# SilentBotStep.net
KiCad netlist of a schematic drawn in Altium Designer
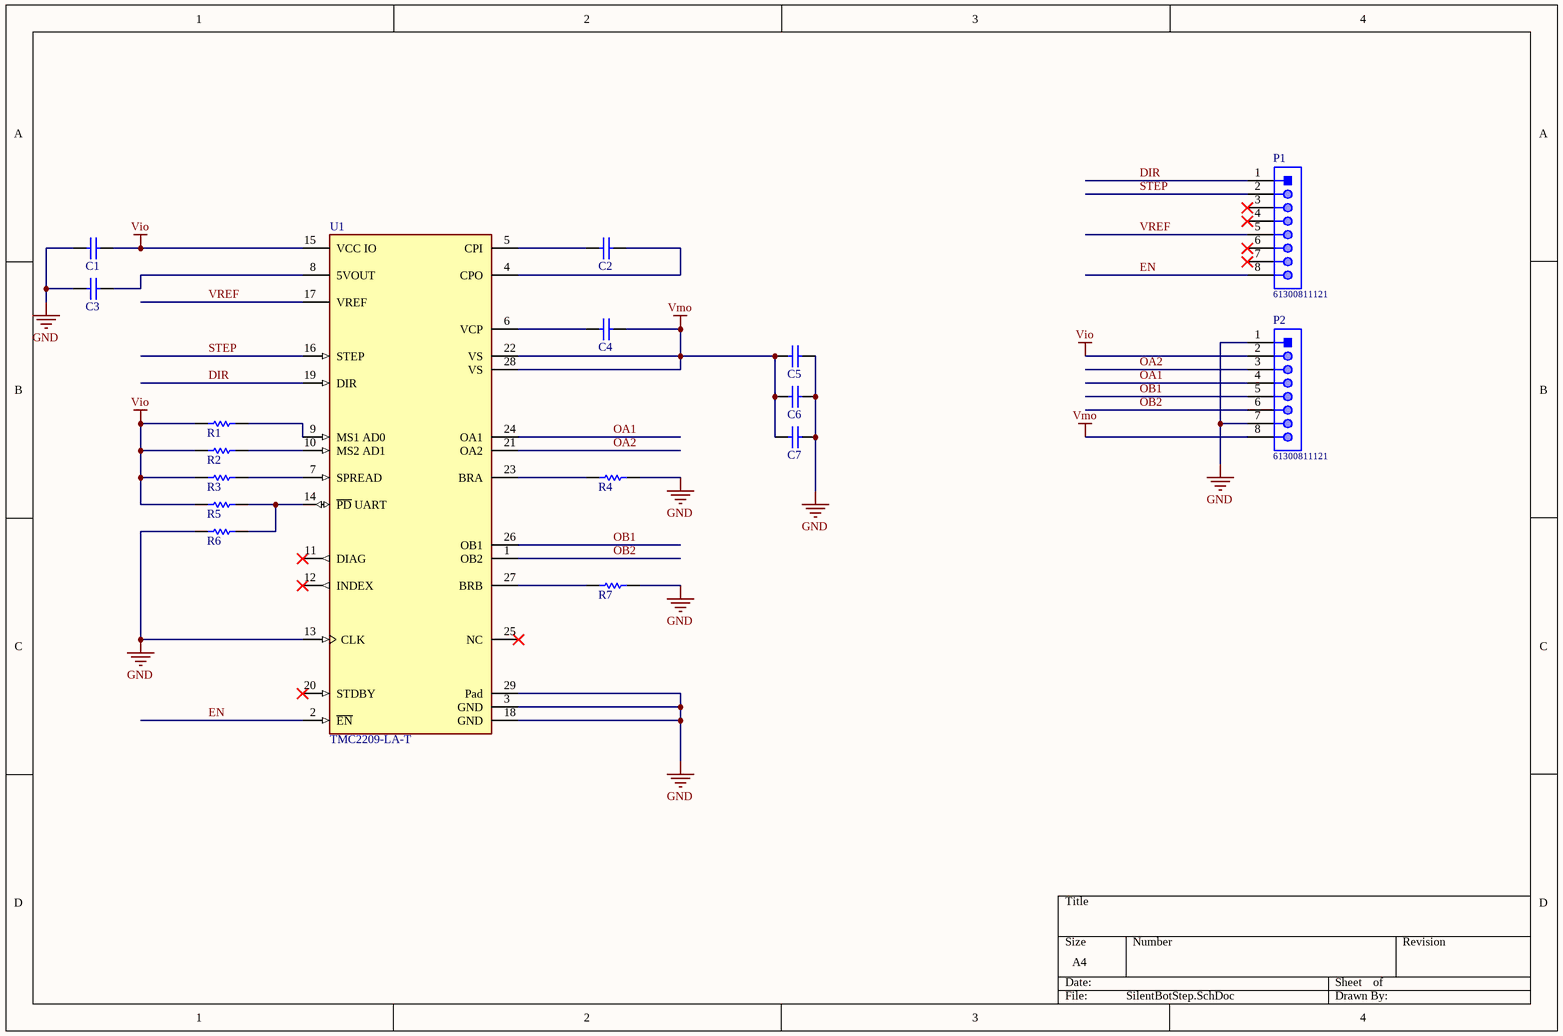
[diagram p0: SilentBotStep.SchDoc]

(export (version "E")
  (design (tool "Eeschema 10.0.6"))
  (components
    (comp (ref "C1")
      (value "GRM155R71H104KE14D")
      (footprint "CAPC1005X55X25LL05T10")
      (description "MURATA - GRM155R71H104KE14D - CAP, MLCC, X7R, 0.1UF, 50V, 0402")
      (fields (field (name "TOLERANCE") "10%") (field (name "VOLTAGE") "50V"))
      (libsource (lib "LTY LLC") (part "CAP"))
    )
    (comp (ref "C2")
      (value "CC0402KRX7R9BB223")
      (footprint "CAPC1005X55X25LL05T10")
      (description "Multilayer Ceramic Capacitors MLCC - SMD/SMT 22K pF 10% 50 Volts")
      (fields (field (name "TOLERANCE") "10%"))
      (libsource (lib "LTY LLC") (part "CAP"))
    )
    (comp (ref "C3")
      (value "GRM155R60J475ME47D")
      (footprint "CAPC1005X55X25LL05T10")
      (description "CAP CER 4.7UF 6.3V X5R 0402")
      (fields (field (name "VOLTAGE") "6.3V") (field (name "TOLERANCE") "20%"))
      (libsource (lib "LTY LLC") (part "CAP"))
    )
    (comp (ref "C4")
      (value "GRM155R71H104KE14D")
      (footprint "CAPC1005X55X25LL05T10")
      (description "MURATA - GRM155R71H104KE14D - CAP, MLCC, X7R, 0.1UF, 50V, 0402")
      (fields (field (name "TOLERANCE") "10%") (field (name "VOLTAGE") "50V"))
      (libsource (lib "LTY LLC") (part "CAP"))
    )
    (comp (ref "C5")
      (value "GRM155R71H104KE14D")
      (footprint "CAPC1005X55X25LL05T10")
      (description "MURATA - GRM155R71H104KE14D - CAP, MLCC, X7R, 0.1UF, 50V, 0402")
      (fields (field (name "TOLERANCE") "10%") (field (name "VOLTAGE") "50V"))
      (libsource (lib "LTY LLC") (part "CAP"))
    )
    (comp (ref "C6")
      (value "GRM155R71H104KE14D")
      (footprint "CAPC1005X55X25LL05T10")
      (description "MURATA - GRM155R71H104KE14D - CAP, MLCC, X7R, 0.1UF, 50V, 0402")
      (fields (field (name "TOLERANCE") "10%") (field (name "VOLTAGE") "50V"))
      (libsource (lib "LTY LLC") (part "CAP"))
    )
    (comp (ref "C7")
      (value "C3216X7R1V106M160AC")
      (footprint "CAPC3216X180X20LL20")
      (fields (field (name "TOLERANCE") "20%"))
      (libsource (lib "LTY LLC") (part "CAP-NP-2"))
    )
    (comp (ref "P1")
      (value "61300811121")
      (footprint "61300811121")
      (description "Board-To-Board Connector, Vertical, Wr-Phd Series, Through Hole, Header, 8, 2.54 Mm")
      (libsource (lib "LTY LLC") (part "WE-CN-1P-M-R8"))
    )
    (comp (ref "P2")
      (value "61300811121")
      (footprint "61300811121")
      (description "Board-To-Board Connector, Vertical, Wr-Phd Series, Through Hole, Header, 8, 2.54 Mm")
      (libsource (lib "LTY LLC") (part "WE-CN-1P-M-R8"))
    )
    (comp (ref "R1")
      (value "RC0402JR-070RL")
      (footprint "RESC1005X40X25LL05T10")
      (description "YAGEO - RC0402JR-070RL. - RES, THICK FILM, 0R, 0.0625W, 0402")
      (fields (field (name "TOLERANCE") "5%"))
      (libsource (lib "LTY LLC") (part "RES"))
    )
    (comp (ref "R2")
      (value "RC0402JR-070RL")
      (footprint "RESC1005X40X25LL05T10")
      (description "YAGEO - RC0402JR-070RL. - RES, THICK FILM, 0R, 0.0625W, 0402")
      (fields (field (name "TOLERANCE") "5%"))
      (libsource (lib "LTY LLC") (part "RES"))
    )
    (comp (ref "R3")
      (value "RC0402JR-070RL")
      (footprint "RESC1005X40X25LL05T10")
      (description "YAGEO - RC0402JR-070RL. - RES, THICK FILM, 0R, 0.0625W, 0402")
      (fields (field (name "TOLERANCE") "5%"))
      (libsource (lib "LTY LLC") (part "RES"))
    )
    (comp (ref "R4")
      (value "ERJ-U6QFR27V")
      (footprint "RESC2013X50X40LL20T20")
      (description "RES 0.27 OHM 1% 1/4W 0805")
      (fields (field (name "TOLERANCE") "1%"))
      (libsource (lib "LTY LLC") (part "RES"))
    )
    (comp (ref "R5")
      (value "RC0402JR-070RL")
      (footprint "RESC1005X40X25LL05T10")
      (description "YAGEO - RC0402JR-070RL. - RES, THICK FILM, 0R, 0.0625W, 0402")
      (fields (field (name "TOLERANCE") "5%"))
      (libsource (lib "LTY LLC") (part "RES"))
    )
    (comp (ref "R6")
      (value "RC0402JR-070RL")
      (footprint "RESC1005X40X25LL05T10")
      (description "YAGEO - RC0402JR-070RL. - RES, THICK FILM, 0R, 0.0625W, 0402")
      (fields (field (name "TOLERANCE") "5%"))
      (libsource (lib "LTY LLC") (part "RES"))
    )
    (comp (ref "R7")
      (value "ERJ-U6QFR27V")
      (footprint "RESC2013X50X40LL20T20")
      (description "RES 0.27 OHM 1% 1/4W 0805")
      (fields (field (name "TOLERANCE") "1%"))
      (libsource (lib "LTY LLC") (part "RES"))
    )
    (comp (ref "U1")
      (value "TMC2209-LA-T")
      (footprint "Trinamic_0_IPC_C")
      (description "Motor Driver, Stepper, QFN-28")
      (libsource (lib "LTY LLC") (part "TMC2209-LA"))
    )
  )
  (nets
    (net (code "1") (name "/DIR") (class "Default")
      (node (ref "P1") (pin "1") (pinfunction "1_1") (pintype "passive"))
      (node (ref "U1") (pin "19") (pinfunction "DIR_19") (pintype "input"))
    )
    (net (code "2") (name "/EN") (class "Default")
      (node (ref "P1") (pin "8") (pinfunction "8_8") (pintype "passive"))
      (node (ref "U1") (pin "2") (pinfunction "~{EN}_2") (pintype "input"))
    )
    (net (code "3") (name "/OA1") (class "Default")
      (node (ref "P2") (pin "4") (pinfunction "4_4") (pintype "passive"))
      (node (ref "U1") (pin "24") (pinfunction "OA1_24") (pintype "passive"))
    )
    (net (code "4") (name "/OA2") (class "Default")
      (node (ref "P2") (pin "3") (pinfunction "3_3") (pintype "passive"))
      (node (ref "U1") (pin "21") (pinfunction "OA2_21") (pintype "passive"))
    )
    (net (code "5") (name "/OB1") (class "Default")
      (node (ref "P2") (pin "5") (pinfunction "5_5") (pintype "passive"))
      (node (ref "U1") (pin "26") (pinfunction "OB1_26") (pintype "passive"))
    )
    (net (code "6") (name "/OB2") (class "Default")
      (node (ref "P2") (pin "6") (pinfunction "6_6") (pintype "passive"))
      (node (ref "U1") (pin "1") (pinfunction "OB2_1") (pintype "passive"))
    )
    (net (code "7") (name "/STEP") (class "Default")
      (node (ref "P1") (pin "2") (pinfunction "2_2") (pintype "passive"))
      (node (ref "U1") (pin "16") (pinfunction "STEP_16") (pintype "input"))
    )
    (net (code "8") (name "/VREF") (class "Default")
      (node (ref "P1") (pin "5") (pinfunction "5_5") (pintype "passive"))
      (node (ref "U1") (pin "17") (pinfunction "VREF_17") (pintype "passive"))
    )
    (net (code "9") (name "GND") (class "Default")
      (node (ref "C1") (pin "1") (pinfunction "1_1") (pintype "passive"))
      (node (ref "C3") (pin "1") (pinfunction "1_1") (pintype "passive"))
      (node (ref "C5") (pin "2") (pinfunction "2_2") (pintype "passive"))
      (node (ref "C6") (pin "2") (pinfunction "2_2") (pintype "passive"))
      (node (ref "C7") (pin "2") (pinfunction "2_2") (pintype "passive"))
      (node (ref "P2") (pin "1") (pinfunction "1_1") (pintype "passive"))
      (node (ref "P2") (pin "7") (pinfunction "7_7") (pintype "passive"))
      (node (ref "R4") (pin "2") (pinfunction "2_2") (pintype "passive"))
      (node (ref "R6") (pin "1") (pinfunction "1_1") (pintype "passive"))
      (node (ref "R7") (pin "2") (pinfunction "2_2") (pintype "passive"))
      (node (ref "U1") (pin "13") (pinfunction "CLK_13") (pintype "input"))
      (node (ref "U1") (pin "18") (pinfunction "GND_18") (pintype "power_in"))
      (node (ref "U1") (pin "29") (pinfunction "Pad_29") (pintype "power_in"))
      (node (ref "U1") (pin "3") (pinfunction "GND_3") (pintype "power_in"))
    )
    (net (code "10") (name "Net-(U1-5VOUT)") (class "Default")
      (node (ref "C3") (pin "2") (pinfunction "2_2") (pintype "passive"))
      (node (ref "U1") (pin "8") (pinfunction "5VOUT_8") (pintype "power_in"))
    )
    (net (code "11") (name "Net-(U1-BRA)") (class "Default")
      (node (ref "R4") (pin "1") (pinfunction "1_1") (pintype "passive"))
      (node (ref "U1") (pin "23") (pinfunction "BRA_23") (pintype "passive"))
    )
    (net (code "12") (name "Net-(U1-BRB)") (class "Default")
      (node (ref "R7") (pin "1") (pinfunction "1_1") (pintype "passive"))
      (node (ref "U1") (pin "27") (pinfunction "BRB_27") (pintype "passive"))
    )
    (net (code "13") (name "Net-(U1-CPI)") (class "Default")
      (node (ref "C2") (pin "1") (pinfunction "1_1") (pintype "passive"))
      (node (ref "U1") (pin "5") (pinfunction "CPI_5") (pintype "passive"))
    )
    (net (code "14") (name "Net-(U1-CPO)") (class "Default")
      (node (ref "C2") (pin "2") (pinfunction "2_2") (pintype "passive"))
      (node (ref "U1") (pin "4") (pinfunction "CPO_4") (pintype "passive"))
    )
    (net (code "15") (name "Net-(U1-MS1_AD0)") (class "Default")
      (node (ref "R1") (pin "2") (pinfunction "2_2") (pintype "passive"))
      (node (ref "U1") (pin "9") (pinfunction "MS1_AD0_9") (pintype "input"))
    )
    (net (code "16") (name "Net-(U1-MS2_AD1)") (class "Default")
      (node (ref "R2") (pin "2") (pinfunction "2_2") (pintype "passive"))
      (node (ref "U1") (pin "10") (pinfunction "MS2_AD1_10") (pintype "input"))
    )
    (net (code "17") (name "Net-(U1-SPREAD)") (class "Default")
      (node (ref "R3") (pin "2") (pinfunction "2_2") (pintype "passive"))
      (node (ref "U1") (pin "7") (pinfunction "SPREAD_7") (pintype "input"))
    )
    (net (code "18") (name "Net-(U1-VCP)") (class "Default")
      (node (ref "C4") (pin "1") (pinfunction "1_1") (pintype "passive"))
      (node (ref "U1") (pin "6") (pinfunction "VCP_6") (pintype "power_in"))
    )
    (net (code "19") (name "Net-(U1-~{PD}_UART)") (class "Default")
      (node (ref "R5") (pin "2") (pinfunction "2_2") (pintype "passive"))
      (node (ref "R6") (pin "2") (pinfunction "2_2") (pintype "passive"))
      (node (ref "U1") (pin "14") (pinfunction "~{PD}_UART_14") (pintype "bidirectional"))
    )
    (net (code "20") (name "Vio") (class "Default")
      (node (ref "C1") (pin "2") (pinfunction "2_2") (pintype "passive"))
      (node (ref "P2") (pin "2") (pinfunction "2_2") (pintype "passive"))
      (node (ref "R1") (pin "1") (pinfunction "1_1") (pintype "passive"))
      (node (ref "R2") (pin "1") (pinfunction "1_1") (pintype "passive"))
      (node (ref "R3") (pin "1") (pinfunction "1_1") (pintype "passive"))
      (node (ref "R5") (pin "1") (pinfunction "1_1") (pintype "passive"))
      (node (ref "U1") (pin "15") (pinfunction "VCC_IO_15") (pintype "power_in"))
    )
    (net (code "21") (name "Vmo") (class "Default")
      (node (ref "C4") (pin "2") (pinfunction "2_2") (pintype "passive"))
      (node (ref "C5") (pin "1") (pinfunction "1_1") (pintype "passive"))
      (node (ref "C6") (pin "1") (pinfunction "1_1") (pintype "passive"))
      (node (ref "C7") (pin "1") (pinfunction "1_1") (pintype "passive"))
      (node (ref "P2") (pin "8") (pinfunction "8_8") (pintype "passive"))
      (node (ref "U1") (pin "22") (pinfunction "VS_22") (pintype "power_in"))
      (node (ref "U1") (pin "28") (pinfunction "VS_28") (pintype "power_in"))
    )
    (net (code "22") (name "unconnected-(P1-Pad3)") (class "Default")
      (node (ref "P1") (pin "3") (pinfunction "3_3") (pintype "passive+no_connect"))
    )
    (net (code "23") (name "unconnected-(P1-Pad4)") (class "Default")
      (node (ref "P1") (pin "4") (pinfunction "4_4") (pintype "passive+no_connect"))
    )
    (net (code "24") (name "unconnected-(P1-Pad6)") (class "Default")
      (node (ref "P1") (pin "6") (pinfunction "6_6") (pintype "passive+no_connect"))
    )
    (net (code "25") (name "unconnected-(P1-Pad7)") (class "Default")
      (node (ref "P1") (pin "7") (pinfunction "7_7") (pintype "passive+no_connect"))
    )
    (net (code "26") (name "unconnected-(U1-DIAG-Pad11)") (class "Default")
      (node (ref "U1") (pin "11") (pinfunction "DIAG_11") (pintype "output+no_connect"))
    )
    (net (code "27") (name "unconnected-(U1-INDEX-Pad12)") (class "Default")
      (node (ref "U1") (pin "12") (pinfunction "INDEX_12") (pintype "output+no_connect"))
    )
    (net (code "28") (name "unconnected-(U1-NC-Pad25)") (class "Default")
      (node (ref "U1") (pin "25") (pinfunction "NC_25") (pintype "passive+no_connect"))
    )
    (net (code "29") (name "unconnected-(U1-STDBY-Pad20)") (class "Default")
      (node (ref "U1") (pin "20") (pinfunction "STDBY_20") (pintype "input+no_connect"))
    )
  )
)
